# uv-dosimeter-guva-op-amp-mk-1_4.net
KiCad netlist of a schematic drawn in EAGLE
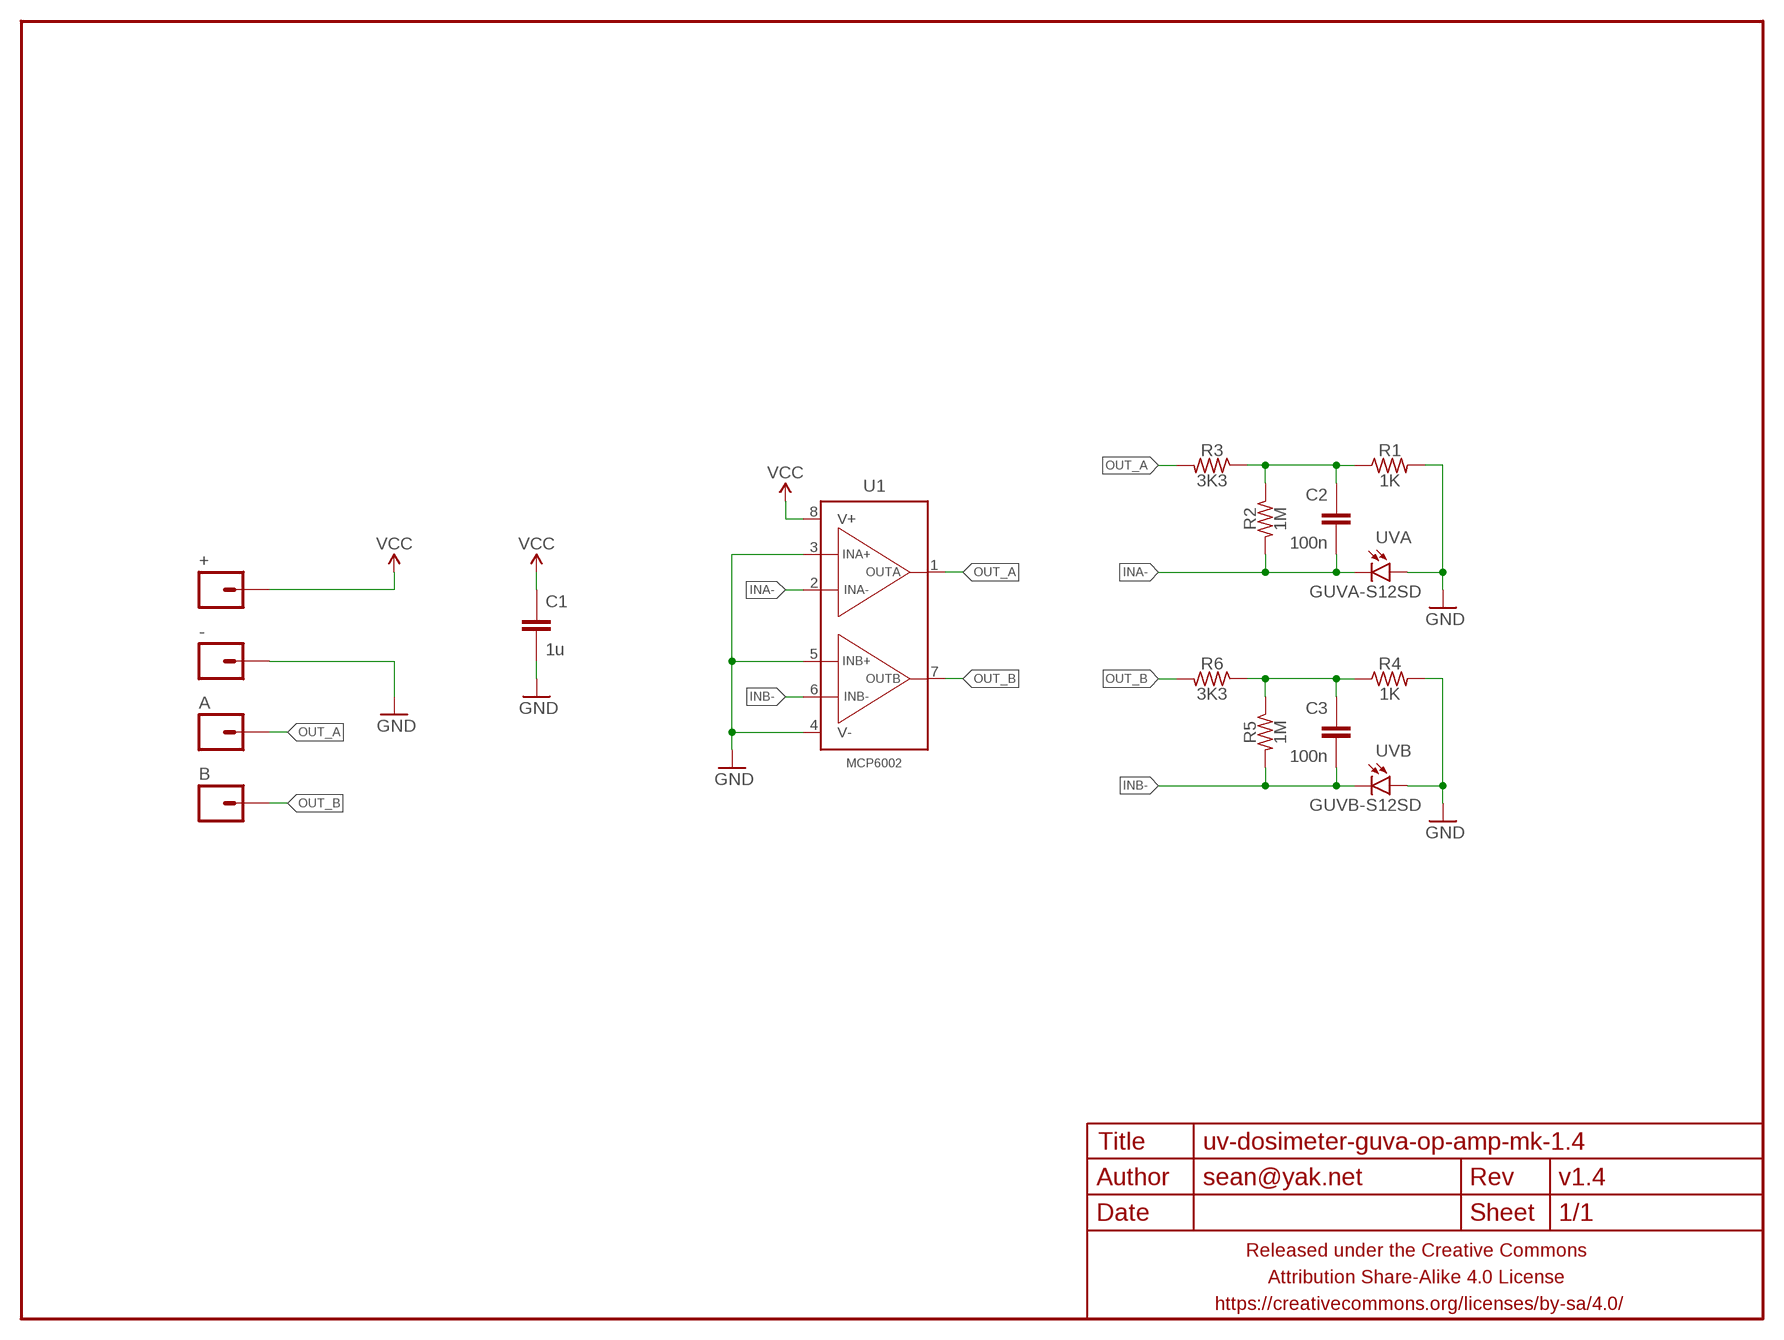
[diagram p0: schematic, sheet 1]

(export (version "E")
  (design (tool "Eeschema 10.0.6"))
  (components
    (comp (ref "+")
      (value "M01PTH")
      (footprint "eagle-import:1X01")
      (libsource (lib "eagle-import") (part "M01PTH"))
    )
    (comp (ref "-")
      (value "M01PTH")
      (footprint "eagle-import:1X01")
      (libsource (lib "eagle-import") (part "M01PTH"))
    )
    (comp (ref "A")
      (value "M01PTH")
      (footprint "eagle-import:1X01")
      (libsource (lib "eagle-import") (part "M01PTH"))
    )
    (comp (ref "B")
      (value "M01PTH")
      (footprint "eagle-import:1X01")
      (libsource (lib "eagle-import") (part "M01PTH"))
    )
    (comp (ref "C1")
      (value "1u")
      (footprint "eagle-import:C0603")
      (libsource (lib "eagle-import") (part "CAPACITOR-CERAMICC0603"))
    )
    (comp (ref "C2")
      (value "100n")
      (footprint "eagle-import:C0603")
      (libsource (lib "eagle-import") (part "CAPACITOR-CERAMICC0603"))
    )
    (comp (ref "C3")
      (value "100n")
      (footprint "eagle-import:C0603")
      (libsource (lib "eagle-import") (part "CAPACITOR-CERAMICC0603"))
    )
    (comp (ref "FRAME1")
      (value "FRAME-LETTERNO_PACKAGE")
      (footprint "eagle-import:DUMMY")
      (fields (field (name "DESIGNER") "sean@yak.net") (field (name "VERSION") "v1.4"))
      (libsource (lib "eagle-import") (part "FRAME-LETTERNO_PACKAGE"))
    )
    (comp (ref "R1")
      (value "1K")
      (footprint "eagle-import:R0603")
      (libsource (lib "eagle-import") (part "RESISTORR0603"))
    )
    (comp (ref "R2")
      (value "1M")
      (footprint "eagle-import:R0603")
      (libsource (lib "eagle-import") (part "RESISTORR0603"))
    )
    (comp (ref "R3")
      (value "3K3")
      (footprint "eagle-import:R0603")
      (libsource (lib "eagle-import") (part "RESISTORR0603"))
    )
    (comp (ref "R4")
      (value "1K")
      (footprint "eagle-import:R0603")
      (libsource (lib "eagle-import") (part "RESISTORR0603"))
    )
    (comp (ref "R5")
      (value "1M")
      (footprint "eagle-import:R0603")
      (libsource (lib "eagle-import") (part "RESISTORR0603"))
    )
    (comp (ref "R6")
      (value "3K3")
      (footprint "eagle-import:R0603")
      (libsource (lib "eagle-import") (part "RESISTORR0603"))
    )
    (comp (ref "U1")
      (value "MCP6002")
      (footprint "eagle-import:SO08")
      (libsource (lib "eagle-import") (part "MCP6002SOIC"))
    )
    (comp (ref "UVA")
      (value "GUVA-S12SD")
      (footprint "eagle-import:LED3528")
      (libsource (lib "eagle-import") (part "GUVA-S12SDLED3528"))
    )
    (comp (ref "UVB")
      (value "GUVB-S12SD")
      (footprint "eagle-import:LED3528")
      (libsource (lib "eagle-import") (part "GUVA-S12SDLED3528"))
    )
  )
  (nets
    (net (code "1") (name "GND") (class "Default")
      (node (ref "-") (pin "1") (pinfunction "1_1") (pintype "passive"))
      (node (ref "C1") (pin "2") (pinfunction "2_2") (pintype "passive"))
      (node (ref "R1") (pin "2") (pinfunction "2_2") (pintype "passive"))
      (node (ref "R4") (pin "2") (pinfunction "2_2") (pintype "passive"))
      (node (ref "U1") (pin "3") (pinfunction "INA+_3") (pintype "input"))
      (node (ref "U1") (pin "4") (pinfunction "V-_4") (pintype "power_in"))
      (node (ref "U1") (pin "5") (pinfunction "INB+_5") (pintype "input"))
      (node (ref "UVA") (pin "A") (pinfunction "A_A") (pintype "passive"))
      (node (ref "UVB") (pin "A") (pinfunction "A_A") (pintype "passive"))
    )
    (net (code "2") (name "INA-") (class "Default")
      (node (ref "C2") (pin "2") (pinfunction "2_2") (pintype "passive"))
      (node (ref "R2") (pin "2") (pinfunction "2_2") (pintype "passive"))
      (node (ref "U1") (pin "2") (pinfunction "INA-_2") (pintype "input"))
      (node (ref "UVA") (pin "K") (pinfunction "C_K") (pintype "passive"))
    )
    (net (code "3") (name "INB-") (class "Default")
      (node (ref "C3") (pin "2") (pinfunction "2_2") (pintype "passive"))
      (node (ref "R5") (pin "2") (pinfunction "2_2") (pintype "passive"))
      (node (ref "U1") (pin "6") (pinfunction "INB-_6") (pintype "input"))
      (node (ref "UVB") (pin "K") (pinfunction "C_K") (pintype "passive"))
    )
    (net (code "4") (name "Net-(C2-Pad1)") (class "Default")
      (node (ref "C2") (pin "1") (pinfunction "1_1") (pintype "passive"))
      (node (ref "R1") (pin "1") (pinfunction "1_1") (pintype "passive"))
      (node (ref "R2") (pin "1") (pinfunction "1_1") (pintype "passive"))
      (node (ref "R3") (pin "1") (pinfunction "1_1") (pintype "passive"))
    )
    (net (code "5") (name "Net-(C3-Pad1)") (class "Default")
      (node (ref "C3") (pin "1") (pinfunction "1_1") (pintype "passive"))
      (node (ref "R4") (pin "1") (pinfunction "1_1") (pintype "passive"))
      (node (ref "R5") (pin "1") (pinfunction "1_1") (pintype "passive"))
      (node (ref "R6") (pin "1") (pinfunction "1_1") (pintype "passive"))
    )
    (net (code "6") (name "OUT_A") (class "Default")
      (node (ref "A") (pin "1") (pinfunction "1_1") (pintype "passive"))
      (node (ref "R3") (pin "2") (pinfunction "2_2") (pintype "passive"))
      (node (ref "U1") (pin "1") (pinfunction "OUTA_1") (pintype "output"))
    )
    (net (code "7") (name "OUT_B") (class "Default")
      (node (ref "B") (pin "1") (pinfunction "1_1") (pintype "passive"))
      (node (ref "R6") (pin "2") (pinfunction "2_2") (pintype "passive"))
      (node (ref "U1") (pin "7") (pinfunction "OUTB_7") (pintype "output"))
    )
    (net (code "8") (name "VCC") (class "Default")
      (node (ref "+") (pin "1") (pinfunction "1_1") (pintype "passive"))
      (node (ref "C1") (pin "1") (pinfunction "1_1") (pintype "passive"))
      (node (ref "U1") (pin "8") (pinfunction "V+_8") (pintype "power_in"))
    )
  )
)
